# body-middle.net
KiCad netlist of a schematic drawn in EAGLE
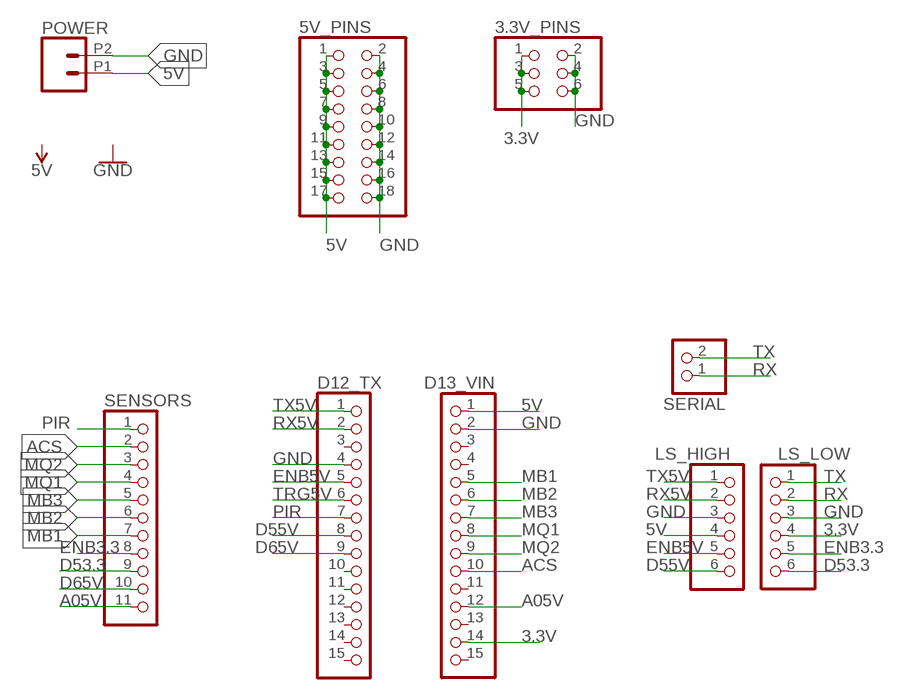
[diagram p0: schematic, sheet 1]

(export (version "E")
  (design (tool "Eeschema 10.0.6"))
  (components
    (comp (ref "3.3V_PINS")
      (value "PINHD-2X3")
      (footprint "eagle-import:2X03")
      (libsource (lib "eagle-import") (part "PINHD-2X3"))
    )
    (comp (ref "5V_PINS")
      (value "PINHD-2X9")
      (footprint "eagle-import:2X09")
      (libsource (lib "eagle-import") (part "PINHD-2X9"))
    )
    (comp (ref "D12_TX")
      (value "PINHD-1X15")
      (footprint "eagle-import:1X15")
      (libsource (lib "eagle-import") (part "PINHD-1X15"))
    )
    (comp (ref "D13_VIN")
      (value "PINHD-1X15")
      (footprint "eagle-import:1X15")
      (libsource (lib "eagle-import") (part "PINHD-1X15"))
    )
    (comp (ref "LS_HIGH")
      (value "PINHD-1X6")
      (footprint "eagle-import:1X06")
      (libsource (lib "eagle-import") (part "PINHD-1X6"))
    )
    (comp (ref "LS_LOW")
      (value "PINHD-1X6")
      (footprint "eagle-import:1X06")
      (libsource (lib "eagle-import") (part "PINHD-1X6"))
    )
    (comp (ref "POWER")
      (value "CONN_022.54MM_SCREWTERM")
      (footprint "eagle-import:1X02_2.54_SCREWTERM")
      (libsource (lib "eagle-import") (part "CONN_022.54MM_SCREWTERM"))
    )
    (comp (ref "SENSORS")
      (value "PINHD-1X11")
      (footprint "eagle-import:1X11")
      (libsource (lib "eagle-import") (part "PINHD-1X11"))
    )
    (comp (ref "SERIAL")
      (value "PINHD-1X2")
      (footprint "eagle-import:1X02")
      (libsource (lib "eagle-import") (part "PINHD-1X2"))
    )
  )
  (nets
    (net (code "1") (name "/3.3V") (class "Default")
      (node (ref "3.3V_PINS") (pin "1") (pinfunction "1_1") (pintype "passive"))
      (node (ref "3.3V_PINS") (pin "3") (pinfunction "3_3") (pintype "passive"))
      (node (ref "3.3V_PINS") (pin "5") (pinfunction "5_5") (pintype "passive"))
      (node (ref "D13_VIN") (pin "14") (pinfunction "14_14") (pintype "passive"))
      (node (ref "LS_LOW") (pin "4") (pinfunction "4_4") (pintype "passive"))
    )
    (net (code "2") (name "/A05V") (class "Default")
      (node (ref "D13_VIN") (pin "12") (pinfunction "12_12") (pintype "passive"))
      (node (ref "SENSORS") (pin "11") (pinfunction "11_11") (pintype "passive"))
    )
    (net (code "3") (name "/D53.3") (class "Default")
      (node (ref "LS_LOW") (pin "6") (pinfunction "6_6") (pintype "passive"))
      (node (ref "SENSORS") (pin "9") (pinfunction "9_9") (pintype "passive"))
    )
    (net (code "4") (name "/D55V") (class "Default")
      (node (ref "D12_TX") (pin "8") (pinfunction "8_8") (pintype "passive"))
      (node (ref "LS_HIGH") (pin "6") (pinfunction "6_6") (pintype "passive"))
    )
    (net (code "5") (name "/D65V") (class "Default")
      (node (ref "D12_TX") (pin "9") (pinfunction "9_9") (pintype "passive"))
      (node (ref "SENSORS") (pin "10") (pinfunction "10_10") (pintype "passive"))
    )
    (net (code "6") (name "/ENB3.3") (class "Default")
      (node (ref "LS_LOW") (pin "5") (pinfunction "5_5") (pintype "passive"))
      (node (ref "SENSORS") (pin "8") (pinfunction "8_8") (pintype "passive"))
    )
    (net (code "7") (name "/ENB5V") (class "Default")
      (node (ref "D12_TX") (pin "5") (pinfunction "5_5") (pintype "passive"))
      (node (ref "LS_HIGH") (pin "5") (pinfunction "5_5") (pintype "passive"))
    )
    (net (code "8") (name "/PIR") (class "Default")
      (node (ref "D12_TX") (pin "7") (pinfunction "7_7") (pintype "passive"))
      (node (ref "SENSORS") (pin "1") (pinfunction "1_1") (pintype "passive"))
    )
    (net (code "9") (name "/RX") (class "Default")
      (node (ref "LS_LOW") (pin "2") (pinfunction "2_2") (pintype "passive"))
      (node (ref "SERIAL") (pin "1") (pinfunction "1_1") (pintype "passive"))
    )
    (net (code "10") (name "/RX5V") (class "Default")
      (node (ref "D12_TX") (pin "2") (pinfunction "2_2") (pintype "passive"))
      (node (ref "LS_HIGH") (pin "2") (pinfunction "2_2") (pintype "passive"))
    )
    (net (code "11") (name "/TRG5V") (class "Default")
      (node (ref "D12_TX") (pin "6") (pinfunction "6_6") (pintype "passive"))
    )
    (net (code "12") (name "/TX") (class "Default")
      (node (ref "LS_LOW") (pin "1") (pinfunction "1_1") (pintype "passive"))
      (node (ref "SERIAL") (pin "2") (pinfunction "2_2") (pintype "passive"))
    )
    (net (code "13") (name "/TX5V") (class "Default")
      (node (ref "D12_TX") (pin "1") (pinfunction "1_1") (pintype "passive"))
      (node (ref "LS_HIGH") (pin "1") (pinfunction "1_1") (pintype "passive"))
    )
    (net (code "14") (name "5V") (class "Default")
      (node (ref "5V_PINS") (pin "1") (pinfunction "1_1") (pintype "passive"))
      (node (ref "5V_PINS") (pin "11") (pinfunction "11_11") (pintype "passive"))
      (node (ref "5V_PINS") (pin "13") (pinfunction "13_13") (pintype "passive"))
      (node (ref "5V_PINS") (pin "15") (pinfunction "15_15") (pintype "passive"))
      (node (ref "5V_PINS") (pin "17") (pinfunction "17_17") (pintype "passive"))
      (node (ref "5V_PINS") (pin "3") (pinfunction "3_3") (pintype "passive"))
      (node (ref "5V_PINS") (pin "5") (pinfunction "5_5") (pintype "passive"))
      (node (ref "5V_PINS") (pin "7") (pinfunction "7_7") (pintype "passive"))
      (node (ref "5V_PINS") (pin "9") (pinfunction "9_9") (pintype "passive"))
      (node (ref "D13_VIN") (pin "1") (pinfunction "1_1") (pintype "passive"))
      (node (ref "LS_HIGH") (pin "4") (pinfunction "4_4") (pintype "passive"))
      (node (ref "POWER") (pin "P1") (pinfunction "1_P1") (pintype "passive"))
    )
    (net (code "15") (name "ACS") (class "Default")
      (node (ref "D13_VIN") (pin "10") (pinfunction "10_10") (pintype "passive"))
      (node (ref "SENSORS") (pin "2") (pinfunction "2_2") (pintype "passive"))
    )
    (net (code "16") (name "GND") (class "Default")
      (node (ref "3.3V_PINS") (pin "2") (pinfunction "2_2") (pintype "passive"))
      (node (ref "3.3V_PINS") (pin "4") (pinfunction "4_4") (pintype "passive"))
      (node (ref "3.3V_PINS") (pin "6") (pinfunction "6_6") (pintype "passive"))
      (node (ref "5V_PINS") (pin "10") (pinfunction "10_10") (pintype "passive"))
      (node (ref "5V_PINS") (pin "12") (pinfunction "12_12") (pintype "passive"))
      (node (ref "5V_PINS") (pin "14") (pinfunction "14_14") (pintype "passive"))
      (node (ref "5V_PINS") (pin "16") (pinfunction "16_16") (pintype "passive"))
      (node (ref "5V_PINS") (pin "18") (pinfunction "18_18") (pintype "passive"))
      (node (ref "5V_PINS") (pin "2") (pinfunction "2_2") (pintype "passive"))
      (node (ref "5V_PINS") (pin "4") (pinfunction "4_4") (pintype "passive"))
      (node (ref "5V_PINS") (pin "6") (pinfunction "6_6") (pintype "passive"))
      (node (ref "5V_PINS") (pin "8") (pinfunction "8_8") (pintype "passive"))
      (node (ref "D12_TX") (pin "4") (pinfunction "4_4") (pintype "passive"))
      (node (ref "D13_VIN") (pin "2") (pinfunction "2_2") (pintype "passive"))
      (node (ref "LS_HIGH") (pin "3") (pinfunction "3_3") (pintype "passive"))
      (node (ref "LS_LOW") (pin "3") (pinfunction "3_3") (pintype "passive"))
      (node (ref "POWER") (pin "P2") (pinfunction "2_P2") (pintype "passive"))
    )
    (net (code "17") (name "MB1") (class "Default")
      (node (ref "D13_VIN") (pin "5") (pinfunction "5_5") (pintype "passive"))
      (node (ref "SENSORS") (pin "7") (pinfunction "7_7") (pintype "passive"))
    )
    (net (code "18") (name "MB2") (class "Default")
      (node (ref "D13_VIN") (pin "6") (pinfunction "6_6") (pintype "passive"))
      (node (ref "SENSORS") (pin "6") (pinfunction "6_6") (pintype "passive"))
    )
    (net (code "19") (name "MB3") (class "Default")
      (node (ref "D13_VIN") (pin "7") (pinfunction "7_7") (pintype "passive"))
      (node (ref "SENSORS") (pin "5") (pinfunction "5_5") (pintype "passive"))
    )
    (net (code "20") (name "MQ1") (class "Default")
      (node (ref "D13_VIN") (pin "8") (pinfunction "8_8") (pintype "passive"))
      (node (ref "SENSORS") (pin "4") (pinfunction "4_4") (pintype "passive"))
    )
    (net (code "21") (name "MQ2") (class "Default")
      (node (ref "D13_VIN") (pin "9") (pinfunction "9_9") (pintype "passive"))
      (node (ref "SENSORS") (pin "3") (pinfunction "3_3") (pintype "passive"))
    )
    (net (code "22") (name "unconnected-(D12_TX-Pad3)") (class "Default")
      (node (ref "D12_TX") (pin "3") (pinfunction "3_3") (pintype "passive"))
    )
    (net (code "23") (name "unconnected-(D12_TX-Pad10)") (class "Default")
      (node (ref "D12_TX") (pin "10") (pinfunction "10_10") (pintype "passive"))
    )
    (net (code "24") (name "unconnected-(D12_TX-Pad11)") (class "Default")
      (node (ref "D12_TX") (pin "11") (pinfunction "11_11") (pintype "passive"))
    )
    (net (code "25") (name "unconnected-(D12_TX-Pad12)") (class "Default")
      (node (ref "D12_TX") (pin "12") (pinfunction "12_12") (pintype "passive"))
    )
    (net (code "26") (name "unconnected-(D12_TX-Pad13)") (class "Default")
      (node (ref "D12_TX") (pin "13") (pinfunction "13_13") (pintype "passive"))
    )
    (net (code "27") (name "unconnected-(D12_TX-Pad14)") (class "Default")
      (node (ref "D12_TX") (pin "14") (pinfunction "14_14") (pintype "passive"))
    )
    (net (code "28") (name "unconnected-(D12_TX-Pad15)") (class "Default")
      (node (ref "D12_TX") (pin "15") (pinfunction "15_15") (pintype "passive"))
    )
    (net (code "29") (name "unconnected-(D13_VIN-Pad3)") (class "Default")
      (node (ref "D13_VIN") (pin "3") (pinfunction "3_3") (pintype "passive"))
    )
    (net (code "30") (name "unconnected-(D13_VIN-Pad4)") (class "Default")
      (node (ref "D13_VIN") (pin "4") (pinfunction "4_4") (pintype "passive"))
    )
    (net (code "31") (name "unconnected-(D13_VIN-Pad11)") (class "Default")
      (node (ref "D13_VIN") (pin "11") (pinfunction "11_11") (pintype "passive"))
    )
    (net (code "32") (name "unconnected-(D13_VIN-Pad13)") (class "Default")
      (node (ref "D13_VIN") (pin "13") (pinfunction "13_13") (pintype "passive"))
    )
    (net (code "33") (name "unconnected-(D13_VIN-Pad15)") (class "Default")
      (node (ref "D13_VIN") (pin "15") (pinfunction "15_15") (pintype "passive"))
    )
  )
)
